# CAN_LIN.net
KiCad netlist of a schematic drawn in Altium Designer
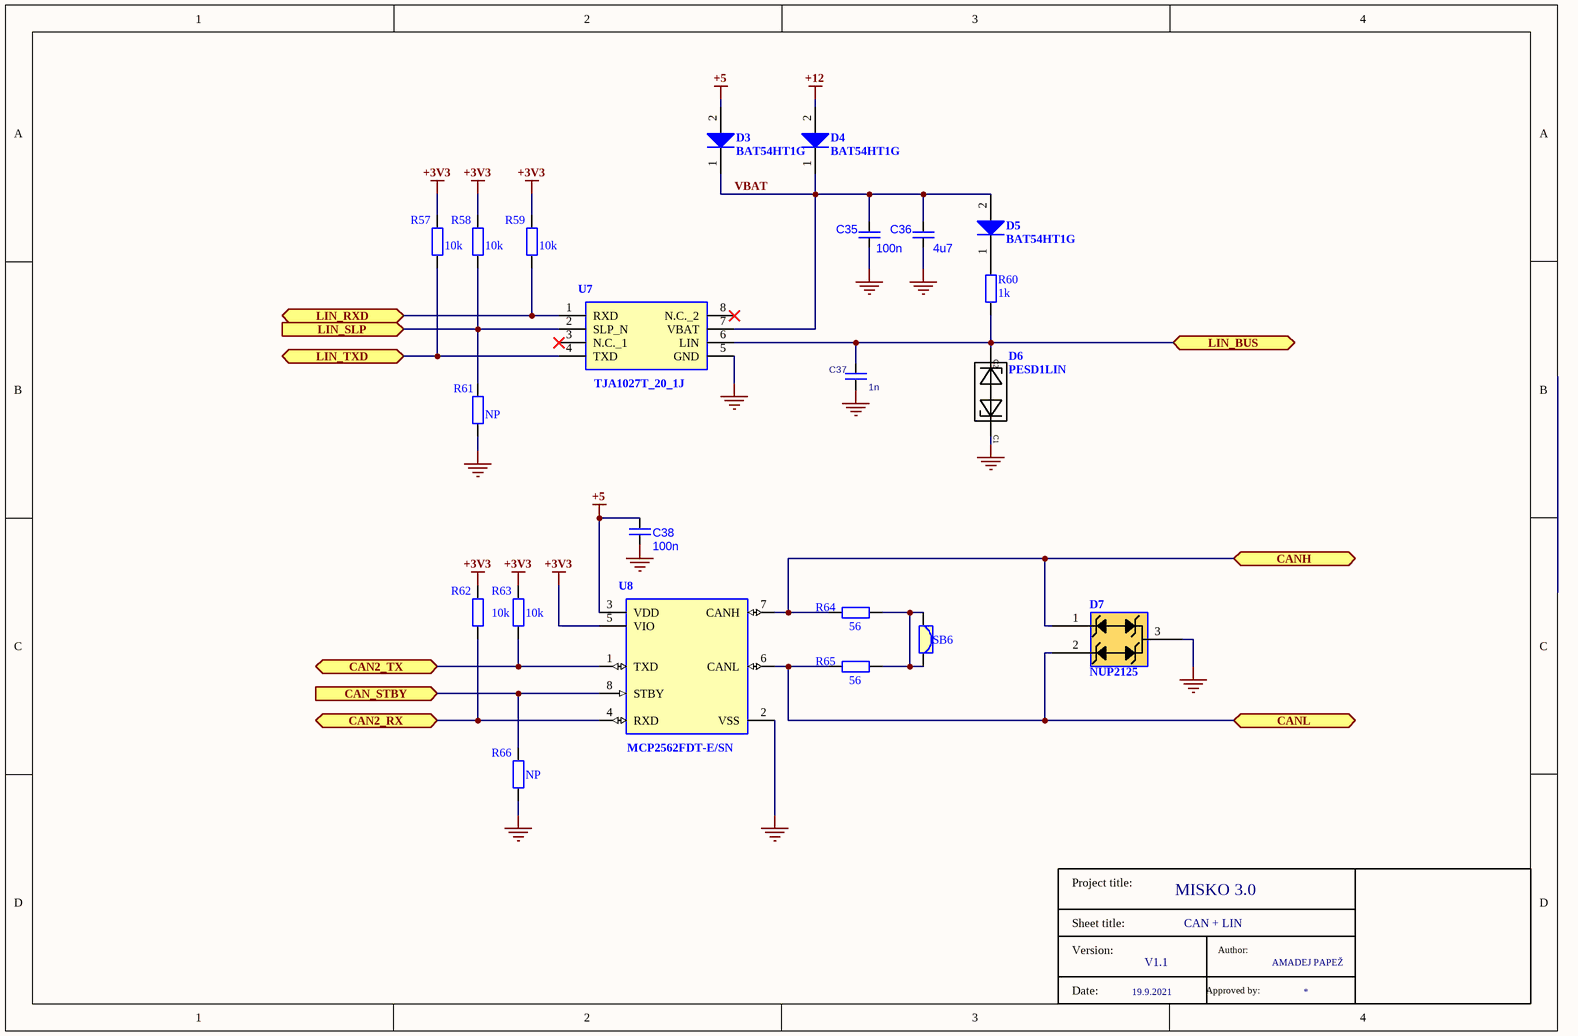
[diagram p0: CAN + LIN.SchDoc]

(export (version "E")
  (design (tool "Eeschema 10.0.6"))
  (components
    (comp (ref "C35")
      (value "100n")
      (footprint "C0603")
      (description "Capacitor")
      (libsource (lib "MISKO3_V6") (part "C"))
    )
    (comp (ref "C36")
      (value "4u7")
      (footprint "C0603")
      (description "Capacitor")
      (libsource (lib "MISKO3_V6") (part "C"))
    )
    (comp (ref "C37")
      (value "1n")
      (footprint "C0603")
      (description "Capacitor")
      (libsource (lib "MISKO3_V6") (part "C"))
    )
    (comp (ref "C38")
      (value "100n")
      (footprint "C0603")
      (description "Capacitor")
      (libsource (lib "MISKO3_V6") (part "C"))
    )
    (comp (ref "D3")
      (value "BAT54HT1G")
      (footprint "ONSC-SOD-323-2-477-02_V")
      (description "Schottky Barrier Diode, 2-Pin SOD-323, Pb-Free, Tape and Reel")
      (fields (field (name "MANUFACTURER") "ON Semiconductor / Fairchild"))
      (libsource (lib "MISKO3_V6") (part "BAT54HT1G"))
    )
    (comp (ref "D4")
      (value "BAT54HT1G")
      (footprint "ONSC-SOD-323-2-477-02_V")
      (description "Schottky Barrier Diode, 2-Pin SOD-323, Pb-Free, Tape and Reel")
      (fields (field (name "MANUFACTURER") "ON Semiconductor / Fairchild"))
      (libsource (lib "MISKO3_V6") (part "BAT54HT1G"))
    )
    (comp (ref "D5")
      (value "BAT54HT1G")
      (footprint "ONSC-SOD-323-2-477-02_V")
      (description "Schottky Barrier Diode, 2-Pin SOD-323, Pb-Free, Tape and Reel")
      (fields (field (name "MANUFACTURER") "ON Semiconductor / Fairchild"))
      (libsource (lib "MISKO3_V6") (part "BAT54HT1G"))
    )
    (comp (ref "D6")
      (value "PESD1LIN")
      (footprint "PESD1LIN_footprint")
      (description "LIN-bus ESD protection diode")
      (libsource (lib "MISKO3_V6") (part "PESD1LIN"))
    )
    (comp (ref "D7")
      (value "NUP2125")
      (footprint "SOT23127P600-8N")
      (libsource (lib "MISKO3_V6") (part "NUP2125"))
    )
    (comp (ref "R57")
      (value "10k")
      (footprint "R1608_0603I_L")
      (description "R")
      (libsource (lib "MISKO3_V6") (part "R"))
    )
    (comp (ref "R58")
      (value "10k")
      (footprint "R1608_0603I_L")
      (description "R")
      (libsource (lib "MISKO3_V6") (part "R"))
    )
    (comp (ref "R59")
      (value "10k")
      (footprint "R1608_0603I_L")
      (description "R")
      (libsource (lib "MISKO3_V6") (part "R"))
    )
    (comp (ref "R60")
      (value "1k")
      (footprint "R1608_0603I_L")
      (description "R")
      (libsource (lib "MISKO3_V6") (part "R"))
    )
    (comp (ref "R61")
      (value "NP")
      (footprint "R1608_0603I_L")
      (description "R")
      (libsource (lib "MISKO3_V6") (part "R"))
    )
    (comp (ref "R62")
      (value "10k")
      (footprint "R1608_0603I_L")
      (description "R")
      (libsource (lib "MISKO3_V6") (part "R"))
    )
    (comp (ref "R63")
      (value "10k")
      (footprint "R1608_0603I_L")
      (description "R")
      (libsource (lib "MISKO3_V6") (part "R"))
    )
    (comp (ref "R64")
      (value "56")
      (footprint "R1608_0603I_L")
      (description "R")
      (libsource (lib "") (part "R_1"))
    )
    (comp (ref "R65")
      (value "56")
      (footprint "R1608_0603I_L")
      (description "R")
      (libsource (lib "") (part "R_1"))
    )
    (comp (ref "R66")
      (value "NP")
      (footprint "R1608_0603I_L")
      (description "R")
      (libsource (lib "MISKO3_V6") (part "R"))
    )
    (comp (ref "SB6")
      (value "SD_JUMP")
      (footprint "SOLDER_JUMPER")
      (libsource (lib "MISKO3_V6") (part "SD_JUMP"))
    )
    (comp (ref "T8") (value "~") (libsource (lib "MISKO3_V6") (part "Title block")))
    (comp (ref "U7")
      (value "TJA1027T_20_1J")
      (footprint "SOIC127P600X175-8N")
      (fields
        (field (name "MANUFACTURER_PART_NUMBER") "TJA1027T/20/1J")
        (field (name "MOUSER PART NUMBER") "771-TJA1027T/20/1J")
      )
      (libsource (lib "MISKO3_V6") (part "TJA1027T_20_1J"))
    )
    (comp (ref "U8")
      (value "MCP2562FDT-E/SN")
      (footprint "FP-C04-057-SN-MFG")
      (description "IC TRANSCEIVER 1/1 8SOIC")
      (libsource (lib "MISKO3_V6") (part "MCP2562FDT-E/SN"))
    )
  )
  (nets
    (net (code "1") (name "+3V3") (class "Default")
      (node (ref "R57") (pin "1") (pintype "passive"))
      (node (ref "R58") (pin "1") (pintype "passive"))
      (node (ref "R59") (pin "1") (pintype "passive"))
      (node (ref "R62") (pin "1") (pintype "passive"))
      (node (ref "R63") (pin "1") (pintype "passive"))
      (node (ref "U8") (pin "5") (pinfunction "VIO_5") (pintype "power_in"))
    )
    (net (code "2") (name "+5") (class "Default")
      (node (ref "C38") (pin "2") (pinfunction "2_2") (pintype "passive"))
      (node (ref "D3") (pin "2") (pinfunction "A_2") (pintype "passive"))
      (node (ref "U8") (pin "3") (pinfunction "VDD_3") (pintype "power_in"))
    )
    (net (code "3") (name "+12") (class "Default")
      (node (ref "D4") (pin "2") (pinfunction "A_2") (pintype "passive"))
    )
    (net (code "4") (name "/CAN2_RX") (class "Default")
      (node (ref "R62") (pin "2") (pintype "passive"))
      (node (ref "U8") (pin "4") (pinfunction "RXD_4") (pintype "bidirectional"))
    )
    (net (code "5") (name "/CAN2_TX") (class "Default")
      (node (ref "R63") (pin "2") (pintype "passive"))
      (node (ref "U8") (pin "1") (pinfunction "TXD_1") (pintype "bidirectional"))
    )
    (net (code "6") (name "/CANH") (class "Default")
      (node (ref "D7") (pin "1") (pinfunction "CANL_1") (pintype "passive"))
      (node (ref "R64") (pin "1") (pintype "passive"))
      (node (ref "U8") (pin "7") (pinfunction "CANH_7") (pintype "bidirectional"))
    )
    (net (code "7") (name "/CANL") (class "Default")
      (node (ref "D7") (pin "2") (pinfunction "CANH_2") (pintype "passive"))
      (node (ref "R65") (pin "1") (pintype "passive"))
      (node (ref "U8") (pin "6") (pinfunction "CANL_6") (pintype "bidirectional"))
    )
    (net (code "8") (name "/CAN_STBY") (class "Default")
      (node (ref "R66") (pin "1") (pintype "passive"))
      (node (ref "U8") (pin "8") (pinfunction "STBY_8") (pintype "input"))
    )
    (net (code "9") (name "/LIN_BUS") (class "Default")
      (node (ref "C37") (pin "1") (pinfunction "1_1") (pintype "passive"))
      (node (ref "D6") (pin "2") (pinfunction "C2_2") (pintype "passive"))
      (node (ref "R60") (pin "2") (pintype "passive"))
      (node (ref "U7") (pin "6") (pinfunction "LIN_6") (pintype "passive"))
    )
    (net (code "10") (name "/LIN_RXD") (class "Default")
      (node (ref "R59") (pin "2") (pintype "passive"))
      (node (ref "U7") (pin "1") (pinfunction "RXD_1") (pintype "passive"))
    )
    (net (code "11") (name "/LIN_SLP") (class "Default")
      (node (ref "R58") (pin "2") (pintype "passive"))
      (node (ref "R61") (pin "2") (pintype "passive"))
      (node (ref "U7") (pin "2") (pinfunction "SLP_N_2") (pintype "passive"))
    )
    (net (code "12") (name "/LIN_TXD") (class "Default")
      (node (ref "R57") (pin "2") (pintype "passive"))
      (node (ref "U7") (pin "4") (pinfunction "TXD_4") (pintype "passive"))
    )
    (net (code "13") (name "/VBAT") (class "Default")
      (node (ref "C35") (pin "2") (pinfunction "2_2") (pintype "passive"))
      (node (ref "C36") (pin "2") (pinfunction "2_2") (pintype "passive"))
      (node (ref "D3") (pin "1") (pinfunction "K_1") (pintype "passive"))
      (node (ref "D4") (pin "1") (pinfunction "K_1") (pintype "passive"))
      (node (ref "D5") (pin "2") (pinfunction "A_2") (pintype "passive"))
      (node (ref "U7") (pin "7") (pinfunction "VBAT_7") (pintype "passive"))
    )
    (net (code "14") (name "GND") (class "Default")
      (node (ref "C35") (pin "1") (pinfunction "1_1") (pintype "passive"))
      (node (ref "C36") (pin "1") (pinfunction "1_1") (pintype "passive"))
      (node (ref "C37") (pin "2") (pinfunction "2_2") (pintype "passive"))
      (node (ref "C38") (pin "1") (pinfunction "1_1") (pintype "passive"))
      (node (ref "D6") (pin "1") (pinfunction "C1_1") (pintype "passive"))
      (node (ref "D7") (pin "3") (pinfunction "GND_3") (pintype "passive"))
      (node (ref "R61") (pin "1") (pintype "passive"))
      (node (ref "R66") (pin "2") (pintype "passive"))
      (node (ref "U7") (pin "5") (pinfunction "GND_5") (pintype "passive"))
      (node (ref "U8") (pin "2") (pinfunction "VSS_2") (pintype "power_in"))
    )
    (net (code "15") (name "Net-(D5-K)") (class "Default")
      (node (ref "D5") (pin "1") (pinfunction "K_1") (pintype "passive"))
      (node (ref "R60") (pin "1") (pintype "passive"))
    )
    (net (code "16") (name "Net-(SB6-37)") (class "Default")
      (node (ref "R64") (pin "2") (pintype "passive"))
      (node (ref "R65") (pin "2") (pintype "passive"))
      (node (ref "SB6") (pin "1") (pinfunction "37_1") (pintype "passive"))
      (node (ref "SB6") (pin "2") (pinfunction "38_2") (pintype "passive"))
    )
    (net (code "17") (name "unconnected-(U7-N.C._1-Pad3)") (class "Default")
      (node (ref "U7") (pin "3") (pinfunction "N.C._1_3") (pintype "passive+no_connect"))
    )
    (net (code "18") (name "unconnected-(U7-N.C._2-Pad8)") (class "Default")
      (node (ref "U7") (pin "8") (pinfunction "N.C._2_8") (pintype "passive+no_connect"))
    )
  )
)
